# design.net
KiCad netlist of a schematic drawn in EasyEDA Pro
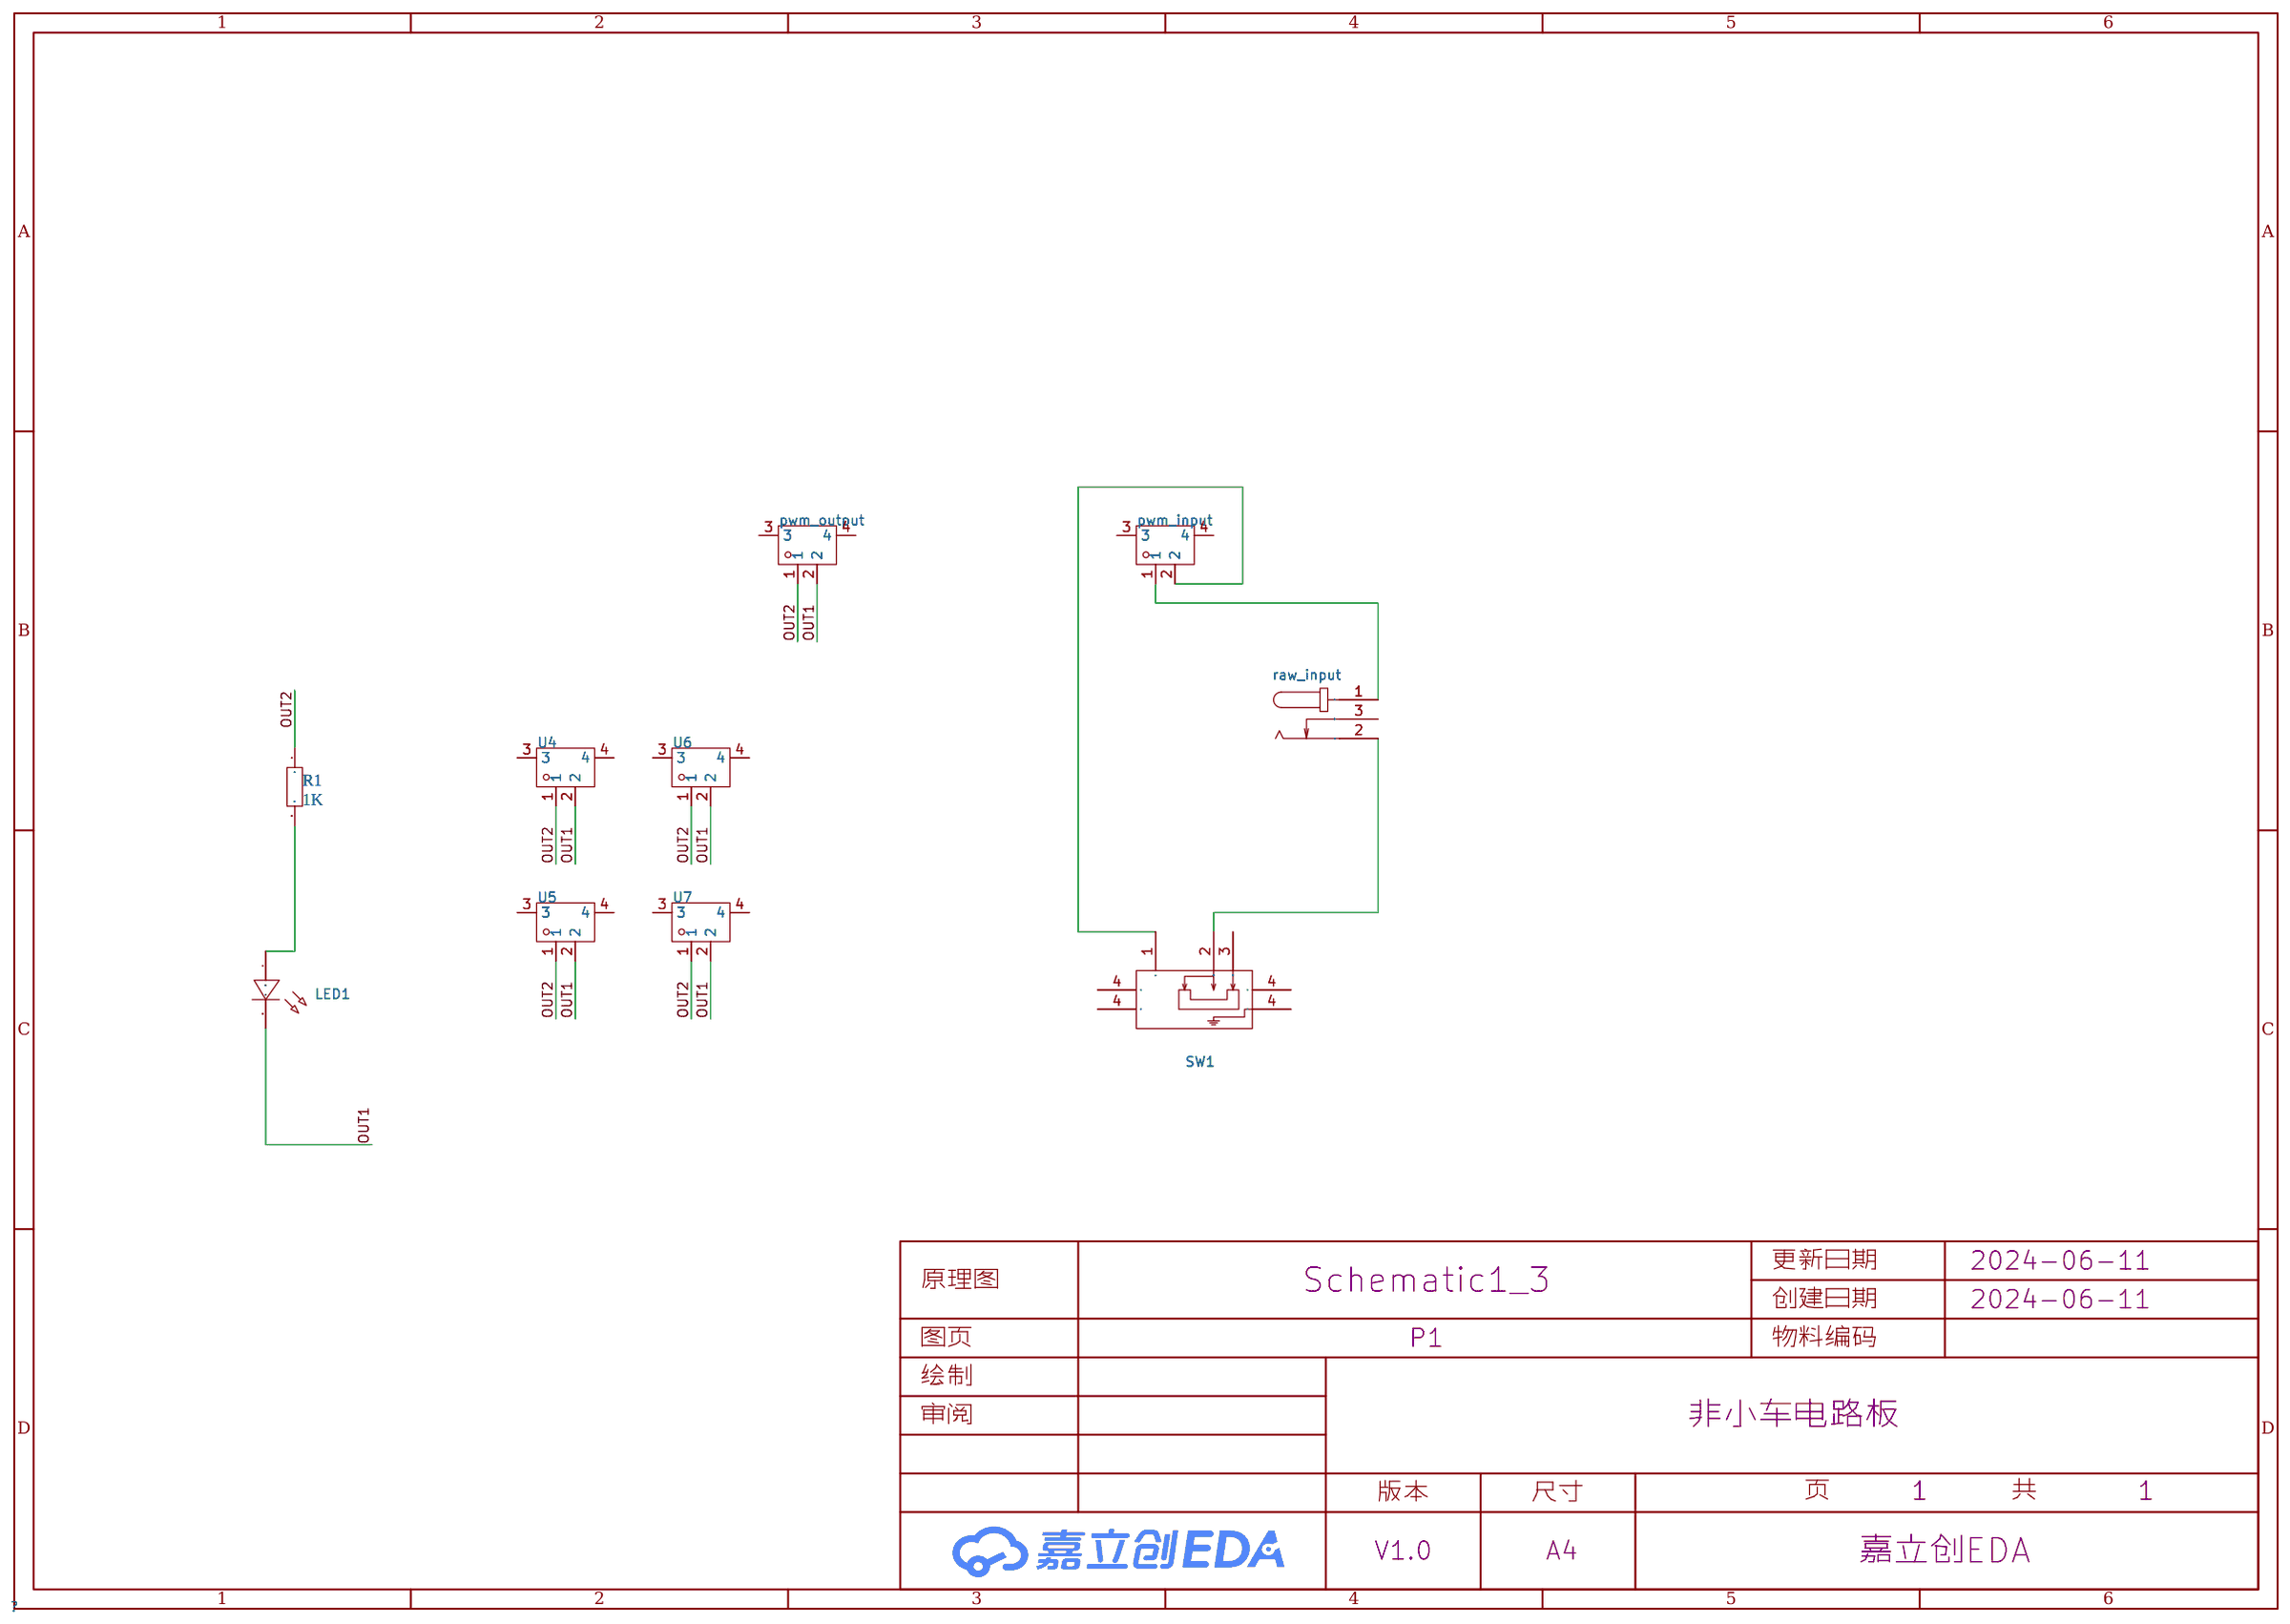
[diagram p0: schematic sheet]

(export (version "E")
  (design (tool "Eeschema 10.0.6"))
  (components
    (comp (ref "LED1")
      (value "~")
      (footprint "easyedapro:LED_TH-3mm")
      (libsource (lib "easyedapro") (part "LED_TH-R"))
    )
    (comp (ref "pwm_input")
      (value "XD-GH-2PWT")
      (footprint "easyedapro:CONN-SMD_GH-2PWT")
      (description "参考系列:GH;间距:1.25mm;插针结构:1x2P;排数:1;每排PIN数:2;公母:公型插针;安装方式:卧贴;额定电流:1A;触头镀层:锡;工作温度范围:-40°C~+105°C;")
      (fields (field (name "Manufacturer") "XUNDA(讯答)"))
      (libsource (lib "easyedapro") (part "XD-GH-2PWT"))
    )
    (comp (ref "pwm_output")
      (value "XD-GH-2PWT")
      (footprint "easyedapro:CONN-SMD_GH-2PWT")
      (description "参考系列:GH;间距:1.25mm;插针结构:1x2P;排数:1;每排PIN数:2;公母:公型插针;安装方式:卧贴;额定电流:1A;触头镀层:锡;工作温度范围:-40°C~+105°C;")
      (fields (field (name "Manufacturer") "XUNDA(讯答)"))
      (libsource (lib "easyedapro") (part "XD-GH-2PWT"))
    )
    (comp (ref "R1")
      (value "1K")
      (footprint "easyedapro:0805-1")
      (description "贴片电阻")
      (fields (field (name "Publisher") "Altium Limited"))
      (libsource (lib "easyedapro") (part "Res1"))
    )
    (comp (ref "raw_input")
      (value "DC-005-A200")
      (footprint "easyedapro:DC-IN-TH_DC-005-A200")
      (description "连接器类型:DC电源插座;安装方式:弯插;触点内径:2mm;触点外径:6.4mm;额定电流:3A;额定电压:30V;工作温度范围:-20°C~+70°C;")
      (fields (field (name "Manufacturer") "XUNPU(讯普)"))
      (libsource (lib "easyedapro") (part "DC-005-A200"))
    )
    (comp (ref "SW1")
      (value "MSK12C02")
      (footprint "easyedapro:SW-TH_MSK12C02")
      (fields (field (name "Manufacturer") "SHOU HAN(首韩)"))
      (libsource (lib "easyedapro") (part "MSK12C02"))
    )
    (comp (ref "U4")
      (value "XD-GH-2PWT")
      (footprint "easyedapro:CONN-SMD_GH-2PWT")
      (description "参考系列:GH;间距:1.25mm;插针结构:1x2P;排数:1;每排PIN数:2;公母:公型插针;安装方式:卧贴;额定电流:1A;触头镀层:锡;工作温度范围:-40°C~+105°C;")
      (fields (field (name "Manufacturer") "XUNDA(讯答)"))
      (libsource (lib "easyedapro") (part "XD-GH-2PWT"))
    )
    (comp (ref "U5")
      (value "XD-GH-2PWT")
      (footprint "easyedapro:CONN-SMD_GH-2PWT")
      (description "参考系列:GH;间距:1.25mm;插针结构:1x2P;排数:1;每排PIN数:2;公母:公型插针;安装方式:卧贴;额定电流:1A;触头镀层:锡;工作温度范围:-40°C~+105°C;")
      (fields (field (name "Manufacturer") "XUNDA(讯答)"))
      (libsource (lib "easyedapro") (part "XD-GH-2PWT"))
    )
    (comp (ref "U6")
      (value "XD-GH-2PWT")
      (footprint "easyedapro:CONN-SMD_GH-2PWT")
      (description "参考系列:GH;间距:1.25mm;插针结构:1x2P;排数:1;每排PIN数:2;公母:公型插针;安装方式:卧贴;额定电流:1A;触头镀层:锡;工作温度范围:-40°C~+105°C;")
      (fields (field (name "Manufacturer") "XUNDA(讯答)"))
      (libsource (lib "easyedapro") (part "XD-GH-2PWT"))
    )
    (comp (ref "U7")
      (value "XD-GH-2PWT")
      (footprint "easyedapro:CONN-SMD_GH-2PWT")
      (description "参考系列:GH;间距:1.25mm;插针结构:1x2P;排数:1;每排PIN数:2;公母:公型插针;安装方式:卧贴;额定电流:1A;触头镀层:锡;工作温度范围:-40°C~+105°C;")
      (fields (field (name "Manufacturer") "XUNDA(讯答)"))
      (libsource (lib "easyedapro") (part "XD-GH-2PWT"))
    )
  )
  (nets
    (net (code "1") (name "/OUT1") (class "Default")
      (node (ref "LED1") (pin "2") (pinfunction "A_2") (pintype "input"))
      (node (ref "U4") (pin "2") (pinfunction "2_2") (pintype "unspecified"))
      (node (ref "U5") (pin "2") (pinfunction "2_2") (pintype "unspecified"))
      (node (ref "U6") (pin "2") (pinfunction "2_2") (pintype "unspecified"))
      (node (ref "U7") (pin "2") (pinfunction "2_2") (pintype "unspecified"))
      (node (ref "pwm_output") (pin "2") (pinfunction "2_2") (pintype "unspecified"))
    )
    (net (code "2") (name "/OUT2") (class "Default")
      (node (ref "R1") (pin "1") (pinfunction "1_1") (pintype "input"))
      (node (ref "U4") (pin "1") (pinfunction "1_1") (pintype "unspecified"))
      (node (ref "U5") (pin "1") (pinfunction "1_1") (pintype "unspecified"))
      (node (ref "U6") (pin "1") (pinfunction "1_1") (pintype "unspecified"))
      (node (ref "U7") (pin "1") (pinfunction "1_1") (pintype "unspecified"))
      (node (ref "pwm_output") (pin "1") (pinfunction "1_1") (pintype "unspecified"))
    )
    (net (code "3") (name "Net-(LED1-C)") (class "Default")
      (node (ref "LED1") (pin "1") (pinfunction "C_1") (pintype "input"))
      (node (ref "R1") (pin "2") (pinfunction "2_2") (pintype "input"))
    )
    (net (code "4") (name "Net-(SW1-Pad1)") (class "Default")
      (node (ref "SW1") (pin "1") (pinfunction "1_1") (pintype "input"))
      (node (ref "pwm_input") (pin "2") (pinfunction "2_2") (pintype "unspecified"))
    )
    (net (code "5") (name "Net-(SW1-Pad2)") (class "Default")
      (node (ref "SW1") (pin "2") (pinfunction "2_2") (pintype "input"))
      (node (ref "raw_input") (pin "2") (pinfunction "2_2") (pintype "unspecified"))
    )
    (net (code "6") (name "Net-(pwm_input-Pad1)") (class "Default")
      (node (ref "pwm_input") (pin "1") (pinfunction "1_1") (pintype "unspecified"))
      (node (ref "raw_input") (pin "1") (pinfunction "1_1") (pintype "unspecified"))
    )
    (net (code "7") (name "unconnected-(SW1-Pad3)") (class "Default")
      (node (ref "SW1") (pin "3") (pinfunction "3_3") (pintype "input"))
    )
    (net (code "8") (name "unconnected-(SW1-Pad4)") (class "Default")
      (node (ref "SW1") (pin "4") (pinfunction "4_4") (pintype "input"))
    )
    (net (code "9") (name "unconnected-(SW1-Pad4)_1") (class "Default")
      (node (ref "SW1") (pin "4") (pinfunction "4_4") (pintype "input"))
    )
    (net (code "10") (name "unconnected-(SW1-Pad4)_2") (class "Default")
      (node (ref "SW1") (pin "4") (pinfunction "4_4") (pintype "input"))
    )
    (net (code "11") (name "unconnected-(SW1-Pad4)_3") (class "Default")
      (node (ref "SW1") (pin "4") (pinfunction "4_4") (pintype "input"))
    )
    (net (code "12") (name "unconnected-(U4-Pad3)") (class "Default")
      (node (ref "U4") (pin "3") (pinfunction "3_3") (pintype "unspecified"))
    )
    (net (code "13") (name "unconnected-(U4-Pad4)") (class "Default")
      (node (ref "U4") (pin "4") (pinfunction "4_4") (pintype "unspecified"))
    )
    (net (code "14") (name "unconnected-(U5-Pad3)") (class "Default")
      (node (ref "U5") (pin "3") (pinfunction "3_3") (pintype "unspecified"))
    )
    (net (code "15") (name "unconnected-(U5-Pad4)") (class "Default")
      (node (ref "U5") (pin "4") (pinfunction "4_4") (pintype "unspecified"))
    )
    (net (code "16") (name "unconnected-(U6-Pad3)") (class "Default")
      (node (ref "U6") (pin "3") (pinfunction "3_3") (pintype "unspecified"))
    )
    (net (code "17") (name "unconnected-(U6-Pad4)") (class "Default")
      (node (ref "U6") (pin "4") (pinfunction "4_4") (pintype "unspecified"))
    )
    (net (code "18") (name "unconnected-(U7-Pad3)") (class "Default")
      (node (ref "U7") (pin "3") (pinfunction "3_3") (pintype "unspecified"))
    )
    (net (code "19") (name "unconnected-(U7-Pad4)") (class "Default")
      (node (ref "U7") (pin "4") (pinfunction "4_4") (pintype "unspecified"))
    )
    (net (code "20") (name "unconnected-(pwm_input-Pad3)") (class "Default")
      (node (ref "pwm_input") (pin "3") (pinfunction "3_3") (pintype "unspecified"))
    )
    (net (code "21") (name "unconnected-(pwm_input-Pad4)") (class "Default")
      (node (ref "pwm_input") (pin "4") (pinfunction "4_4") (pintype "unspecified"))
    )
    (net (code "22") (name "unconnected-(pwm_output-Pad3)") (class "Default")
      (node (ref "pwm_output") (pin "3") (pinfunction "3_3") (pintype "unspecified"))
    )
    (net (code "23") (name "unconnected-(pwm_output-Pad4)") (class "Default")
      (node (ref "pwm_output") (pin "4") (pinfunction "4_4") (pintype "unspecified"))
    )
    (net (code "24") (name "unconnected-(raw_input-Pad3)") (class "Default")
      (node (ref "raw_input") (pin "3") (pinfunction "3_3") (pintype "unspecified"))
    )
  )
)
